# Microcontroller.net
KiCad netlist of a schematic drawn in Altium Designer
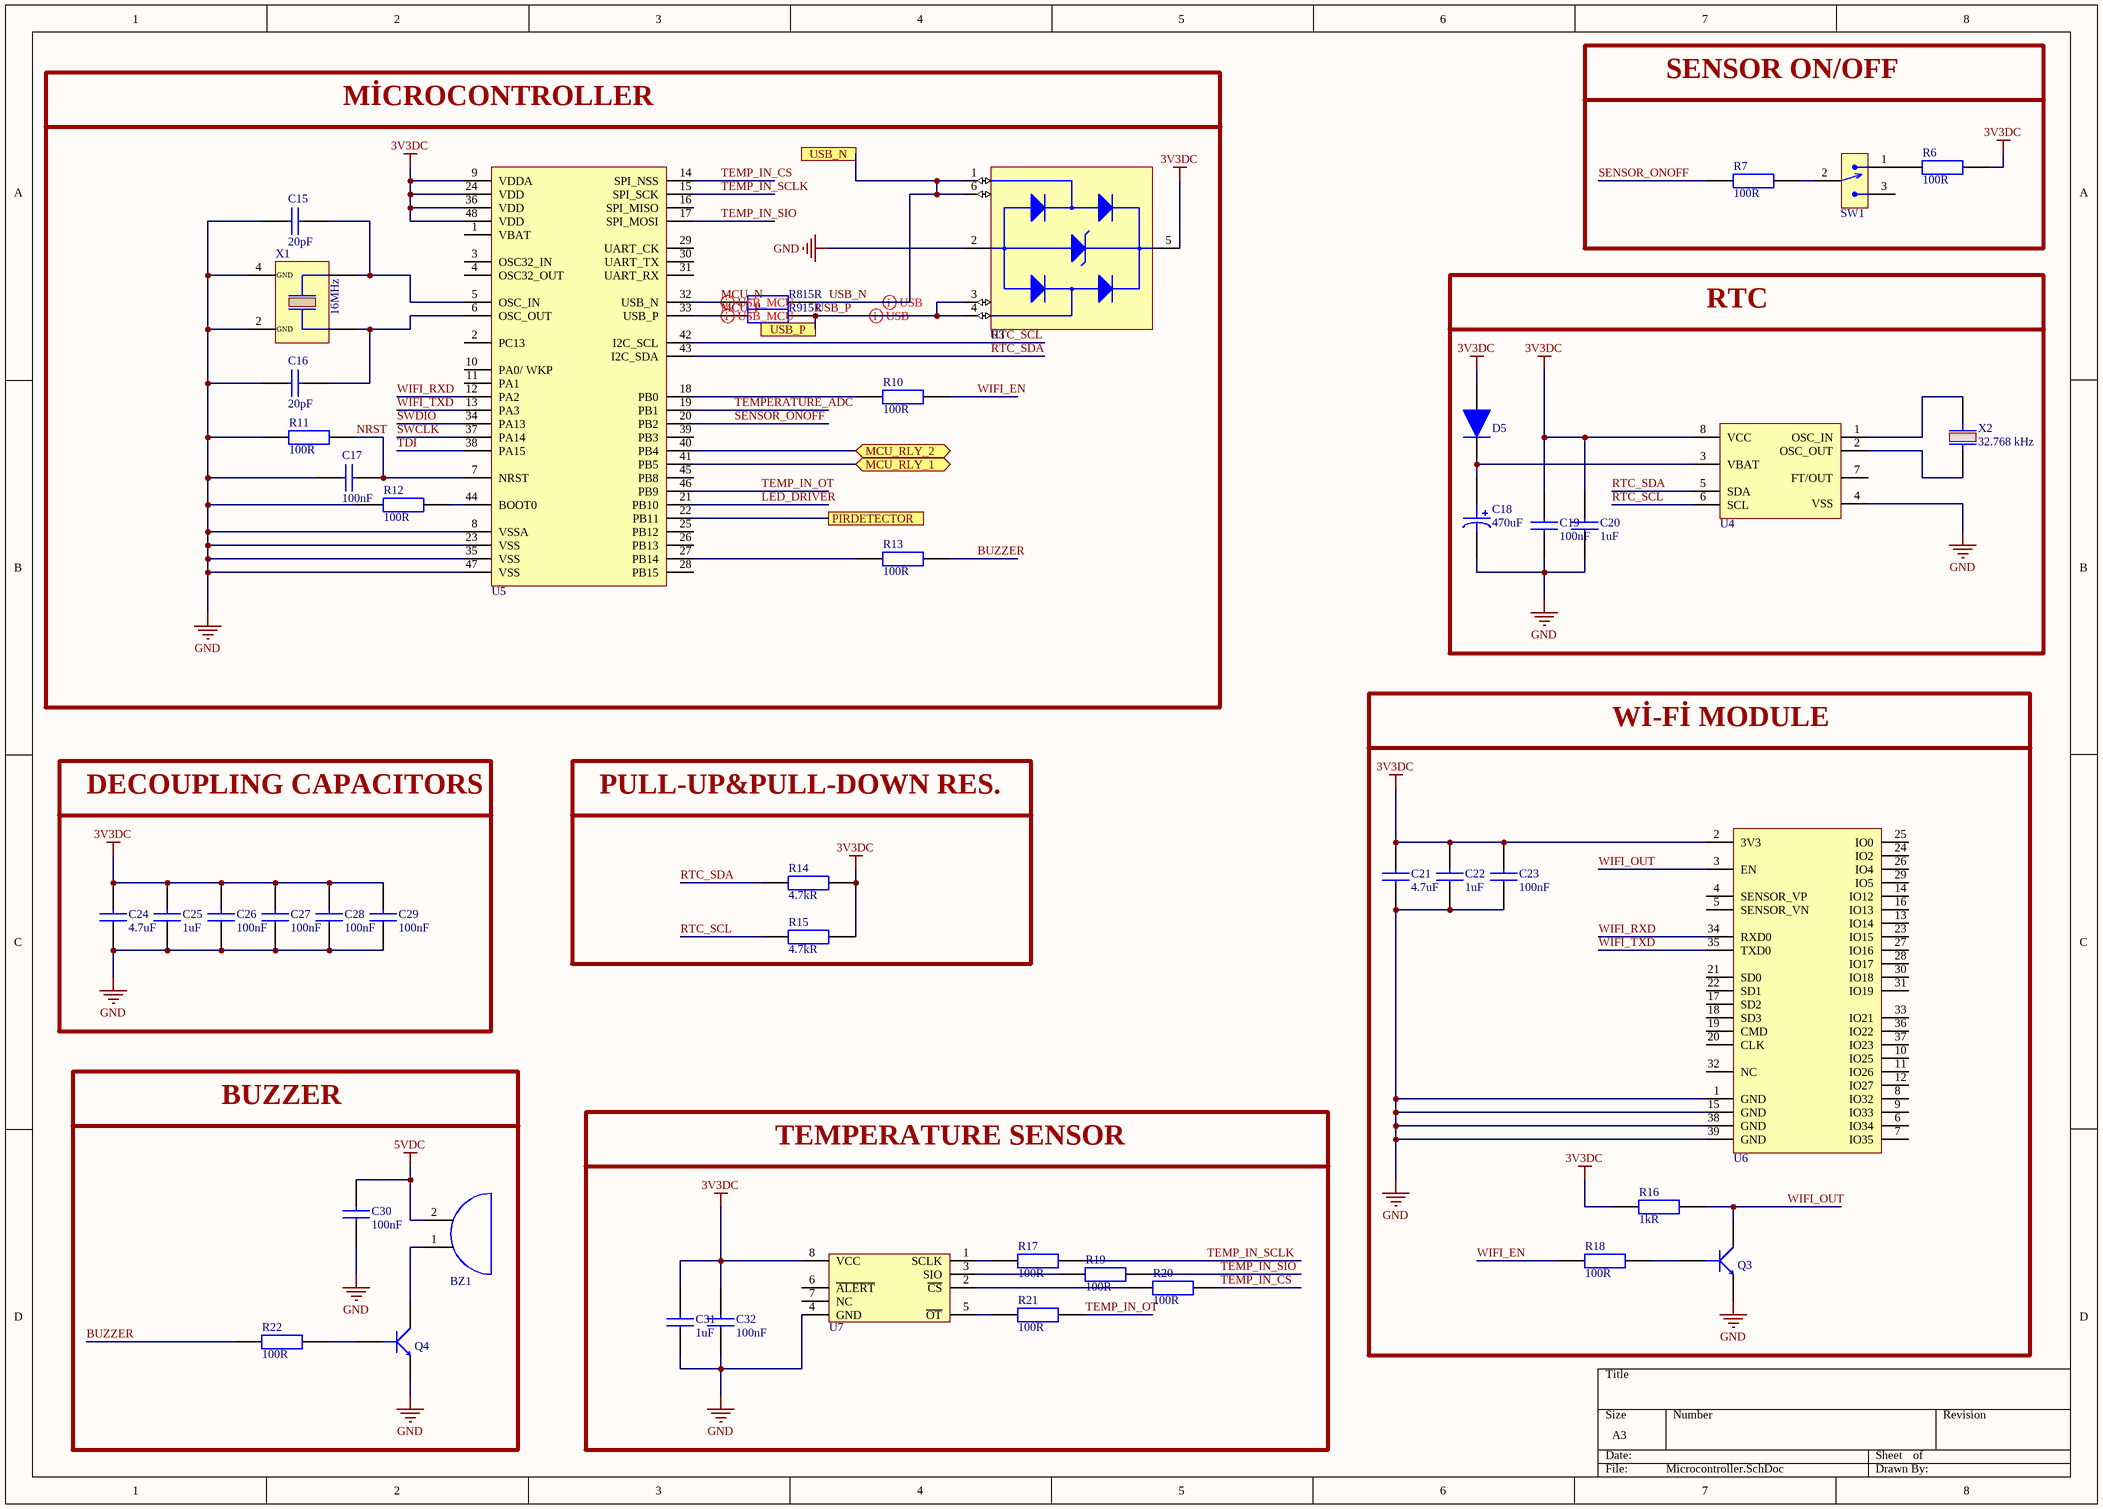
[diagram p0: Microcontroller.SchDoc]

(export (version "E")
  (design (tool "Eeschema 10.0.6"))
  (components
    (comp (ref "BZ1")
      (value "CMI-9605IC-0580T")
      (footprint "CMI-9605IC-0580T")
      (description "Buzzers Indicator, Internally Driven Magnetic 30mA 2.7kHz 80dB @ 5V, 10cm Through Hole PC Pins")
      (fields (field (name "MANUFACTURER") "CUI Devices") (field (name "DESIGNED BY") "TALAT"))
      (libsource (lib "Udemy_Library") (part "CMI-9605IC-0580T"))
    )
    (comp (ref "C15")
      (value "CL10C200JB8NNNC")
      (footprint "CAP_0603")
      (description "CAP CER 20pF %5 0603 SMD")
      (fields
        (field (name "MANUFACTURER") "Samsung")
        (field (name "TOLERANCE") "5%")
        (field (name "CAPACITANCE") "20pF")
        (field (name "DESIGNED BY") "TALAT")
      )
      (libsource (lib "Udemy_Library") (part "CAP CER 20pF 0603"))
    )
    (comp (ref "C16")
      (value "CL10C200JB8NNNC")
      (footprint "CAP_0603")
      (description "CAP CER 20pF %5 0603 SMD")
      (fields
        (field (name "MANUFACTURER") "Samsung")
        (field (name "TOLERANCE") "5%")
        (field (name "CAPACITANCE") "20pF")
        (field (name "DESIGNED BY") "TALAT")
      )
      (libsource (lib "Udemy_Library") (part "CAP CER 20pF 0603"))
    )
    (comp (ref "C17")
      (value "CL21B104KBCNNNC")
      (footprint "CAP_0805")
      (description "CAP CER 100nF %10 0805")
      (fields
        (field (name "MANUFACTURER") "Samsung")
        (field (name "TOLERANCE") "10%")
        (field (name "CAPACITANCE") "100nF")
        (field (name "DESIGNED BY") "TALAT")
      )
      (libsource (lib "Udemy_Library") (part "CAP CER 100nF 0805"))
    )
    (comp (ref "C18")
      (value "ESH477M050AH4AA")
      (footprint "CAP_RADİAL_D10_P5")
      (description "CAP ALU ELEC 470uF 50V RADIAL")
      (fields
        (field (name "MANUFACTURER") "KEMET")
        (field (name "TOLERANCE") "20%")
        (field (name "CAPACITANCE") "470uF")
        (field (name "DESIGNED BY") "TALAT")
      )
      (libsource (lib "Udemy_Library") (part "CAP ALU ELEC 470uF 50V"))
    )
    (comp (ref "C19")
      (value "CL21B104KBCNNNC")
      (footprint "CAP_0805")
      (description "CAP CER 100nF %10 0805")
      (fields
        (field (name "MANUFACTURER") "Samsung")
        (field (name "TOLERANCE") "10%")
        (field (name "CAPACITANCE") "100nF")
        (field (name "DESIGNED BY") "TALAT")
      )
      (libsource (lib "Udemy_Library") (part "CAP CER 100nF 0805"))
    )
    (comp (ref "C20")
      (value "CL21B105KBFNNNE")
      (footprint "CAP_0805")
      (description "CAP CER 1uF %10 0805")
      (fields
        (field (name "MANUFACTURER") "Samsung")
        (field (name "TOLERANCE") "10%")
        (field (name "CAPACITANCE") "1uF")
        (field (name "DESIGNED BY") "TALAT")
      )
      (libsource (lib "Udemy_Library") (part "CAP CER 1uF 0805"))
    )
    (comp (ref "C21")
      (value "CL21A475KAQNNNE")
      (footprint "CAP_0805")
      (description "CAP CER 4.7uF %10 0805")
      (fields
        (field (name "MANUFACTURER") "Samsung")
        (field (name "TOLERANCE") "10%")
        (field (name "CAPACITANCE") "4.7uF")
        (field (name "DESIGNED BY") "TALAT")
      )
      (libsource (lib "Udemy_Library") (part "CAP CER 4.7uF 0805"))
    )
    (comp (ref "C22")
      (value "CL21B105KBFNNNE")
      (footprint "CAP_0805")
      (description "CAP CER 1uF %10 0805")
      (fields
        (field (name "MANUFACTURER") "Samsung")
        (field (name "TOLERANCE") "10%")
        (field (name "CAPACITANCE") "1uF")
        (field (name "DESIGNED BY") "TALAT")
      )
      (libsource (lib "Udemy_Library") (part "CAP CER 1uF 0805"))
    )
    (comp (ref "C23")
      (value "CL21B104KBCNNNC")
      (footprint "CAP_0805")
      (description "CAP CER 100nF %10 0805")
      (fields
        (field (name "MANUFACTURER") "Samsung")
        (field (name "TOLERANCE") "10%")
        (field (name "CAPACITANCE") "100nF")
        (field (name "DESIGNED BY") "TALAT")
      )
      (libsource (lib "Udemy_Library") (part "CAP CER 100nF 0805"))
    )
    (comp (ref "C24")
      (value "CL21A475KAQNNNE")
      (footprint "CAP_0805")
      (description "CAP CER 4.7uF %10 0805")
      (fields
        (field (name "MANUFACTURER") "Samsung")
        (field (name "TOLERANCE") "10%")
        (field (name "CAPACITANCE") "4.7uF")
        (field (name "DESIGNED BY") "TALAT")
      )
      (libsource (lib "Udemy_Library") (part "CAP CER 4.7uF 0805"))
    )
    (comp (ref "C25")
      (value "CL21B105KBFNNNE")
      (footprint "CAP_0805")
      (description "CAP CER 1uF %10 0805")
      (fields
        (field (name "MANUFACTURER") "Samsung")
        (field (name "TOLERANCE") "10%")
        (field (name "CAPACITANCE") "1uF")
        (field (name "DESIGNED BY") "TALAT")
      )
      (libsource (lib "Udemy_Library") (part "CAP CER 1uF 0805"))
    )
    (comp (ref "C26")
      (value "CL21B104KBCNNNC")
      (footprint "CAP_0805")
      (description "CAP CER 100nF %10 0805")
      (fields
        (field (name "MANUFACTURER") "Samsung")
        (field (name "TOLERANCE") "10%")
        (field (name "CAPACITANCE") "100nF")
        (field (name "DESIGNED BY") "TALAT")
      )
      (libsource (lib "Udemy_Library") (part "CAP CER 100nF 0805"))
    )
    (comp (ref "C27")
      (value "CL21B104KBCNNNC")
      (footprint "CAP_0805")
      (description "CAP CER 100nF %10 0805")
      (fields
        (field (name "MANUFACTURER") "Samsung")
        (field (name "TOLERANCE") "10%")
        (field (name "CAPACITANCE") "100nF")
        (field (name "DESIGNED BY") "TALAT")
      )
      (libsource (lib "Udemy_Library") (part "CAP CER 100nF 0805"))
    )
    (comp (ref "C28")
      (value "CL21B104KBCNNNC")
      (footprint "CAP_0805")
      (description "CAP CER 100nF %10 0805")
      (fields
        (field (name "MANUFACTURER") "Samsung")
        (field (name "TOLERANCE") "10%")
        (field (name "CAPACITANCE") "100nF")
        (field (name "DESIGNED BY") "TALAT")
      )
      (libsource (lib "Udemy_Library") (part "CAP CER 100nF 0805"))
    )
    (comp (ref "C29")
      (value "CL21B104KBCNNNC")
      (footprint "CAP_0805")
      (description "CAP CER 100nF %10 0805")
      (fields
        (field (name "MANUFACTURER") "Samsung")
        (field (name "TOLERANCE") "10%")
        (field (name "CAPACITANCE") "100nF")
        (field (name "DESIGNED BY") "TALAT")
      )
      (libsource (lib "Udemy_Library") (part "CAP CER 100nF 0805"))
    )
    (comp (ref "C30")
      (value "CL21B104KBCNNNC")
      (footprint "CAP_0805")
      (description "CAP CER 100nF %10 0805")
      (fields
        (field (name "MANUFACTURER") "Samsung")
        (field (name "TOLERANCE") "10%")
        (field (name "CAPACITANCE") "100nF")
        (field (name "DESIGNED BY") "TALAT")
      )
      (libsource (lib "Udemy_Library") (part "CAP CER 100nF 0805"))
    )
    (comp (ref "C31")
      (value "CL21B105KBFNNNE")
      (footprint "CAP_0805")
      (description "CAP CER 1uF %10 0805")
      (fields
        (field (name "MANUFACTURER") "Samsung")
        (field (name "TOLERANCE") "10%")
        (field (name "CAPACITANCE") "1uF")
        (field (name "DESIGNED BY") "TALAT")
      )
      (libsource (lib "Udemy_Library") (part "CAP CER 1uF 0805"))
    )
    (comp (ref "C32")
      (value "CL21B104KBCNNNC")
      (footprint "CAP_0805")
      (description "CAP CER 100nF %10 0805")
      (fields
        (field (name "MANUFACTURER") "Samsung")
        (field (name "TOLERANCE") "10%")
        (field (name "CAPACITANCE") "100nF")
        (field (name "DESIGNED BY") "TALAT")
      )
      (libsource (lib "Udemy_Library") (part "CAP CER 100nF 0805"))
    )
    (comp (ref "D5")
      (value "1N4148WS")
      (footprint "SOD323F")
      (description "Diode, Single, 75 V, 150 mA, 1 V, 4 ns")
      (fields
        (field (name "MANUFACTURER") "ON Semiconductor / Fairchild")
        (field (name "DESIGNED BY") "TALAT")
      )
      (libsource (lib "Udemy_Library") (part "1N4148WS"))
    )
    (comp (ref "Q3")
      (value "MMBT3904-7-F")
      (footprint "SOT-23F")
      (description "Transistor General Purpose BJT NPN 40 Volt 0.2A Automotive 3-Pin SOT-23")
      (fields (field (name "MANUFACTURER") "Diodes Zetex") (field (name "DESIGNED BY") "TALAT"))
      (libsource (lib "Udemy_Library") (part "MMBT3904-7-F"))
    )
    (comp (ref "Q4")
      (value "MMBT3904-7-F")
      (footprint "SOT-23F")
      (description "Transistor General Purpose BJT NPN 40 Volt 0.2A Automotive 3-Pin SOT-23")
      (fields (field (name "MANUFACTURER") "Diodes Zetex") (field (name "DESIGNED BY") "TALAT"))
      (libsource (lib "Udemy_Library") (part "MMBT3904-7-F"))
    )
    (comp (ref "R6")
      (value "RC0603JR-07100RL")
      (footprint "RES_0603")
      (description "RES 100 %5 OHM 0603 SMD")
      (fields
        (field (name "MANUFACTURER") "Yageo")
        (field (name "TOLERANCE") "5%")
        (field (name "RESISTANCE") "100R")
        (field (name "DESIGNED BY") "TALAT")
      )
      (libsource (lib "") (part "RES 100 OHM 0603_1"))
    )
    (comp (ref "R7")
      (value "RC0603JR-07100RL")
      (footprint "RES_0603")
      (description "RES 100 %5 OHM 0603 SMD")
      (fields
        (field (name "MANUFACTURER") "Yageo")
        (field (name "TOLERANCE") "5%")
        (field (name "RESISTANCE") "100R")
        (field (name "DESIGNED BY") "TALAT")
      )
      (libsource (lib "") (part "RES 100 OHM 0603_1"))
    )
    (comp (ref "R8")
      (value "RC0603JR-0715RL")
      (footprint "RES_0603")
      (description "RES 15 %5 OHM 0603 SMD")
      (fields
        (field (name "MANUFACTURER") "Yageo")
        (field (name "TOLERANCE") "5%")
        (field (name "RESISTANCE") "15R")
        (field (name "DESIGNED BY") "TALAT")
      )
      (libsource (lib "Udemy_Library") (part "RES 15 OHM 0603"))
    )
    (comp (ref "R9")
      (value "RC0603JR-0715RL")
      (footprint "RES_0603")
      (description "RES 15 %5 OHM 0603 SMD")
      (fields
        (field (name "MANUFACTURER") "Yageo")
        (field (name "TOLERANCE") "5%")
        (field (name "RESISTANCE") "15R")
        (field (name "DESIGNED BY") "TALAT")
      )
      (libsource (lib "Udemy_Library") (part "RES 15 OHM 0603"))
    )
    (comp (ref "R10")
      (value "RC0603JR-07100RL")
      (footprint "RES_0603")
      (description "RES 100 %5 OHM 0603 SMD")
      (fields
        (field (name "MANUFACTURER") "Yageo")
        (field (name "TOLERANCE") "5%")
        (field (name "RESISTANCE") "100R")
        (field (name "DESIGNED BY") "TALAT")
      )
      (libsource (lib "Udemy_Library") (part "RES 100 OHM 0603"))
    )
    (comp (ref "R11")
      (value "RC0603JR-07100RL")
      (footprint "RES_0603")
      (description "RES 100 %5 OHM 0603 SMD")
      (fields
        (field (name "MANUFACTURER") "Yageo")
        (field (name "TOLERANCE") "5%")
        (field (name "RESISTANCE") "100R")
        (field (name "DESIGNED BY") "TALAT")
      )
      (libsource (lib "Udemy_Library") (part "RES 100 OHM 0603"))
    )
    (comp (ref "R12")
      (value "RC0603JR-07100RL")
      (footprint "RES_0603")
      (description "RES 100 %5 OHM 0603 SMD")
      (fields
        (field (name "MANUFACTURER") "Yageo")
        (field (name "TOLERANCE") "5%")
        (field (name "RESISTANCE") "100R")
        (field (name "DESIGNED BY") "TALAT")
      )
      (libsource (lib "Udemy_Library") (part "RES 100 OHM 0603"))
    )
    (comp (ref "R13")
      (value "RC0603JR-07100RL")
      (footprint "RES_0603")
      (description "RES 100 %5 OHM 0603 SMD")
      (fields
        (field (name "MANUFACTURER") "Yageo")
        (field (name "TOLERANCE") "5%")
        (field (name "RESISTANCE") "100R")
        (field (name "DESIGNED BY") "TALAT")
      )
      (libsource (lib "Udemy_Library") (part "RES 100 OHM 0603"))
    )
    (comp (ref "R14")
      (value "RC0603JR-074K7L")
      (footprint "RES_0603")
      (description "RES 4K7 %5 OHM 0603 SMD")
      (fields
        (field (name "MANUFACTURER") "Yageo")
        (field (name "TOLERANCE") "5%")
        (field (name "RESISTANCE") "4.7kR")
        (field (name "DESIGNED BY") "TALAT")
      )
      (libsource (lib "Udemy_Library") (part "RES 4K7 OHM 0603"))
    )
    (comp (ref "R15")
      (value "RC0603JR-074K7L")
      (footprint "RES_0603")
      (description "RES 4K7 %5 OHM 0603 SMD")
      (fields
        (field (name "MANUFACTURER") "Yageo")
        (field (name "TOLERANCE") "5%")
        (field (name "RESISTANCE") "4.7kR")
        (field (name "DESIGNED BY") "TALAT")
      )
      (libsource (lib "Udemy_Library") (part "RES 4K7 OHM 0603"))
    )
    (comp (ref "R16")
      (value "RC0603FR-0710KL")
      (footprint "RES_0603")
      (description "RES 1K %1 OHM 0603 SMD")
      (fields
        (field (name "MANUFACTURER") "Yageo")
        (field (name "MANUFACTURER PART NUMBER") "RC0603JR-071KL")
        (field (name "RESISTANCE") "1kR")
        (field (name "DESIGNED BY") "TALAT")
      )
      (libsource (lib "Udemy_Library") (part "RES 1K OHM 0603"))
    )
    (comp (ref "R17")
      (value "RC0603JR-07100RL")
      (footprint "RES_0603")
      (description "RES 100 %5 OHM 0603 SMD")
      (fields
        (field (name "MANUFACTURER") "Yageo")
        (field (name "TOLERANCE") "5%")
        (field (name "RESISTANCE") "100R")
        (field (name "DESIGNED BY") "TALAT")
      )
      (libsource (lib "Udemy_Library") (part "RES 100 OHM 0603"))
    )
    (comp (ref "R18")
      (value "RC0603JR-07100RL")
      (footprint "RES_0603")
      (description "RES 100 %5 OHM 0603 SMD")
      (fields
        (field (name "MANUFACTURER") "Yageo")
        (field (name "TOLERANCE") "5%")
        (field (name "RESISTANCE") "100R")
        (field (name "DESIGNED BY") "TALAT")
      )
      (libsource (lib "Udemy_Library") (part "RES 100 OHM 0603"))
    )
    (comp (ref "R19")
      (value "RC0603JR-07100RL")
      (footprint "RES_0603")
      (description "RES 100 %5 OHM 0603 SMD")
      (fields
        (field (name "MANUFACTURER") "Yageo")
        (field (name "TOLERANCE") "5%")
        (field (name "RESISTANCE") "100R")
        (field (name "DESIGNED BY") "TALAT")
      )
      (libsource (lib "Udemy_Library") (part "RES 100 OHM 0603"))
    )
    (comp (ref "R20")
      (value "RC0603JR-07100RL")
      (footprint "RES_0603")
      (description "RES 100 %5 OHM 0603 SMD")
      (fields
        (field (name "MANUFACTURER") "Yageo")
        (field (name "TOLERANCE") "5%")
        (field (name "RESISTANCE") "100R")
        (field (name "DESIGNED BY") "TALAT")
      )
      (libsource (lib "Udemy_Library") (part "RES 100 OHM 0603"))
    )
    (comp (ref "R21")
      (value "RC0603JR-07100RL")
      (footprint "RES_0603")
      (description "RES 100 %5 OHM 0603 SMD")
      (fields
        (field (name "MANUFACTURER") "Yageo")
        (field (name "TOLERANCE") "5%")
        (field (name "RESISTANCE") "100R")
        (field (name "DESIGNED BY") "TALAT")
      )
      (libsource (lib "Udemy_Library") (part "RES 100 OHM 0603"))
    )
    (comp (ref "R22")
      (value "RC0603JR-07100RL")
      (footprint "RES_0603")
      (description "RES 100 %5 OHM 0603 SMD")
      (fields
        (field (name "MANUFACTURER") "Yageo")
        (field (name "TOLERANCE") "5%")
        (field (name "RESISTANCE") "100R")
        (field (name "DESIGNED BY") "TALAT")
      )
      (libsource (lib "Udemy_Library") (part "RES 100 OHM 0603"))
    )
    (comp (ref "SW1")
      (value "EG1215AA")
      (footprint "EG1215AA")
      (description "Slide Switch, SPDT, 0.025A, 24V, SMD")
      (fields
        (field (name "MANUFACTURER") "E-Switch")
        (field (name "TOLERANCE") "4.95%")
        (field (name "DESIGNED BY") "TALAT")
      )
      (libsource (lib "Udemy_Library") (part "EG1215AA"))
    )
    (comp (ref "U3")
      (value "USBLC6-2SC6")
      (footprint "SOT23-6L")
      (description "TVS DIODE 5.25V 17V SOT23-6")
      (fields (field (name "MANUFACTURER") "STMicroelectronics") (field (name "DESIGNED BY") "TALAT"))
      (libsource (lib "Udemy_Library") (part "USB PROTECTION"))
    )
    (comp (ref "U4")
      (value "M41T00M6F")
      (footprint "SOIC8")
      (description "IC RTC CLK/CALENDAR I2C 8-SOIC")
      (fields (field (name "MANUFACTURER") "STMicroelectronics") (field (name "DESIGNED BY") "TALAT"))
      (libsource (lib "Udemy_Library") (part "M41T00M6F"))
    )
    (comp (ref "U5")
      (value "STM32F103C6T6A")
      (footprint "LQFP-48")
      (description "MCU 32-bit STM32F ARM Cortex M3 RISC 32KB Flash 2.5V/3.3V 48-Pin LQFP Tray")
      (fields (field (name "MANUFACTURER") "STMicroelectronics") (field (name "DESIGNED BY") "TALAT"))
      (libsource (lib "Udemy_Library") (part "STM32F103C6T6A"))
    )
    (comp (ref "U6")
      (value "ESP32-WROOM-32E (4MB)")
      (footprint "ESP32-32")
      (fields
        (field (name "MANUFACTURER") "Espressif Systems")
        (field (name "MANUFACTURER PART NUMBER") "ESP32-WROOM-32E(4MB)")
        (field (name "DESIGNED BY") "TALAT")
      )
      (libsource (lib "Udemy_Library") (part "ESP32-WROOM-32E (4MB)"))
    )
    (comp (ref "U7")
      (value "MAX6662")
      (footprint "SOIC8")
      (description "Temp Sensor Digital Serial (3-Wire, SPI) 8-Pin SOIC N Tube")
      (fields
        (field (name "MANUFACTURER") "Maxim")
        (field (name "MANUFACTURER PART NUMBER") "MAX6662MSA+")
        (field (name "DESIGNED BY") "TALAT")
      )
      (libsource (lib "Udemy_Library") (part "MAX6662"))
    )
    (comp (ref "X1")
      (value "ECS-160-20-30B-TR")
      (footprint "ECS")
      (description "CRYSTAL 16.0000MHZ 20PF SMD")
      (fields
        (field (name "MANUFACTURER") "ECS International")
        (field (name "TOLERANCE") "50ppm")
        (field (name "FREQUENCY") "16MHz")
        (field (name "DESIGNED BY") "TALAT")
      )
      (libsource (lib "Udemy_Library") (part "CRYSTAL 16MHz"))
    )
    (comp (ref "X2")
      (value "ABS05-32.768KHZ-T")
      (footprint "ABS05")
      (description "Crystal, 32.768 kHz, SMD, 1.6mm x 1mm, 12.5 pF, 20 ppm, ABS05 Series")
      (fields
        (field (name "MANUFACTURER") "Abracon")
        (field (name "TOLERANCE") "20ppm")
        (field (name "OPERATING FREQUENCY") "32.768 kHz")
        (field (name "DESIGNED BY") "TALAT")
      )
      (libsource (lib "Udemy_Library") (part "CRYSTAL 32768kHZ"))
    )
  )
  (nets
    (net (code "1") (name "/BUZZER") (class "Default")
      (node (ref "R13") (pin "2") (pinfunction "2_2") (pintype "passive"))
      (node (ref "R22") (pin "1") (pinfunction "1_1") (pintype "passive"))
    )
    (net (code "2") (name "/LED_DRIVER") (class "Default")
      (node (ref "U5") (pin "21") (pinfunction "PB10_21") (pintype "passive"))
    )
    (net (code "3") (name "/MCU_N") (class "Default")
      (node (ref "R8") (pin "1") (pinfunction "1_1") (pintype "passive"))
      (node (ref "U5") (pin "32") (pinfunction "USB_N_32") (pintype "passive"))
    )
    (net (code "4") (name "/MCU_P") (class "Default")
      (node (ref "R9") (pin "1") (pinfunction "1_1") (pintype "passive"))
      (node (ref "U5") (pin "33") (pinfunction "USB_P_33") (pintype "passive"))
    )
    (net (code "5") (name "/MCU_RLY_1") (class "Default")
      (node (ref "U5") (pin "41") (pinfunction "PB5_41") (pintype "passive"))
    )
    (net (code "6") (name "/MCU_RLY_2") (class "Default")
      (node (ref "U5") (pin "40") (pinfunction "PB4_40") (pintype "passive"))
    )
    (net (code "7") (name "/NRST") (class "Default")
      (node (ref "C17") (pin "2") (pinfunction "2_2") (pintype "passive"))
      (node (ref "R11") (pin "2") (pinfunction "2_2") (pintype "passive"))
      (node (ref "U5") (pin "7") (pinfunction "NRST_7") (pintype "passive"))
    )
    (net (code "8") (name "/PIRDETECTOR") (class "Default")
      (node (ref "U5") (pin "22") (pinfunction "PB11_22") (pintype "passive"))
    )
    (net (code "9") (name "/RTC_SCL") (class "Default")
      (node (ref "R15") (pin "1") (pinfunction "1_1") (pintype "passive"))
      (node (ref "U4") (pin "6") (pinfunction "SCL_6") (pintype "passive"))
      (node (ref "U5") (pin "42") (pinfunction "I2C_SCL_42") (pintype "passive"))
    )
    (net (code "10") (name "/RTC_SDA") (class "Default")
      (node (ref "R14") (pin "1") (pinfunction "1_1") (pintype "passive"))
      (node (ref "U4") (pin "5") (pinfunction "SDA_5") (pintype "passive"))
      (node (ref "U5") (pin "43") (pinfunction "I2C_SDA_43") (pintype "passive"))
    )
    (net (code "11") (name "/SENSOR_ONOFF") (class "Default")
      (node (ref "R7") (pin "2") (pinfunction "2_2") (pintype "passive"))
      (node (ref "U5") (pin "20") (pinfunction "PB2_20") (pintype "passive"))
    )
    (net (code "12") (name "/SWCLK") (class "Default")
      (node (ref "U5") (pin "37") (pinfunction "PA14_37") (pintype "passive"))
    )
    (net (code "13") (name "/SWDIO") (class "Default")
      (node (ref "U5") (pin "34") (pinfunction "PA13_34") (pintype "passive"))
    )
    (net (code "14") (name "/TDI") (class "Default")
      (node (ref "U5") (pin "38") (pinfunction "PA15_38") (pintype "passive"))
    )
    (net (code "15") (name "/TEMPERATURE_ADC") (class "Default")
      (node (ref "U5") (pin "19") (pinfunction "PB1_19") (pintype "passive"))
    )
    (net (code "16") (name "/TEMP_IN_CS") (class "Default")
      (node (ref "R20") (pin "2") (pinfunction "2_2") (pintype "passive"))
      (node (ref "U5") (pin "14") (pinfunction "SPI_NSS_14") (pintype "passive"))
    )
    (net (code "17") (name "/TEMP_IN_OT") (class "Default")
      (node (ref "R21") (pin "2") (pinfunction "2_2") (pintype "passive"))
      (node (ref "U5") (pin "46") (pinfunction "PB9_46") (pintype "passive"))
    )
    (net (code "18") (name "/TEMP_IN_SCLK") (class "Default")
      (node (ref "R17") (pin "2") (pinfunction "2_2") (pintype "passive"))
      (node (ref "U5") (pin "15") (pinfunction "SPI_SCK_15") (pintype "passive"))
    )
    (net (code "19") (name "/TEMP_IN_SIO") (class "Default")
      (node (ref "R19") (pin "2") (pinfunction "2_2") (pintype "passive"))
      (node (ref "U5") (pin "17") (pinfunction "SPI_MOSI_17") (pintype "passive"))
    )
    (net (code "20") (name "/USB_N") (class "Default")
      (node (ref "R8") (pin "2") (pinfunction "2_2") (pintype "passive"))
      (node (ref "U3") (pin "1") (pinfunction "I/O1_1") (pintype "bidirectional"))
      (node (ref "U3") (pin "6") (pinfunction "I/O1_6") (pintype "bidirectional"))
    )
    (net (code "21") (name "/USB_P") (class "Default")
      (node (ref "R9") (pin "2") (pinfunction "2_2") (pintype "passive"))
      (node (ref "U3") (pin "3") (pinfunction "I/O2_3") (pintype "bidirectional"))
      (node (ref "U3") (pin "4") (pinfunction "I/O2_4") (pintype "bidirectional"))
    )
    (net (code "22") (name "/WIFI_EN") (class "Default")
      (node (ref "R10") (pin "2") (pinfunction "2_2") (pintype "passive"))
      (node (ref "R18") (pin "1") (pinfunction "1_1") (pintype "passive"))
    )
    (net (code "23") (name "/WIFI_OUT") (class "Default")
      (node (ref "Q3") (pin "3") (pinfunction "C_3") (pintype "power_in"))
      (node (ref "R16") (pin "2") (pinfunction "2_2") (pintype "passive"))
      (node (ref "U6") (pin "3") (pinfunction "EN_3") (pintype "passive"))
    )
    (net (code "24") (name "/WIFI_RXD") (class "Default")
      (node (ref "U5") (pin "12") (pinfunction "PA2_12") (pintype "passive"))
      (node (ref "U6") (pin "34") (pinfunction "RXD0_34") (pintype "passive"))
    )
    (net (code "25") (name "/WIFI_TXD") (class "Default")
      (node (ref "U5") (pin "13") (pinfunction "PA3_13") (pintype "passive"))
      (node (ref "U6") (pin "35") (pinfunction "TXD0_35") (pintype "passive"))
    )
    (net (code "26") (name "3V3DC") (class "Default")
      (node (ref "C19") (pin "2") (pinfunction "2_2") (pintype "passive"))
      (node (ref "C20") (pin "2") (pinfunction "2_2") (pintype "passive"))
      (node (ref "C21") (pin "2") (pinfunction "2_2") (pintype "passive"))
      (node (ref "C22") (pin "2") (pinfunction "2_2") (pintype "passive"))
      (node (ref "C23") (pin "2") (pinfunction "2_2") (pintype "passive"))
      (node (ref "C24") (pin "2") (pinfunction "2_2") (pintype "passive"))
      (node (ref "C25") (pin "2") (pinfunction "2_2") (pintype "passive"))
      (node (ref "C26") (pin "2") (pinfunction "2_2") (pintype "passive"))
      (node (ref "C27") (pin "2") (pinfunction "2_2") (pintype "passive"))
      (node (ref "C28") (pin "2") (pinfunction "2_2") (pintype "passive"))
      (node (ref "C29") (pin "2") (pinfunction "2_2") (pintype "passive"))
      (node (ref "C31") (pin "2") (pinfunction "2_2") (pintype "passive"))
      (node (ref "C32") (pin "2") (pinfunction "2_2") (pintype "passive"))
      (node (ref "D5") (pin "2") (pinfunction "2_2") (pintype "power_in"))
      (node (ref "R14") (pin "2") (pinfunction "2_2") (pintype "passive"))
      (node (ref "R15") (pin "2") (pinfunction "2_2") (pintype "passive"))
      (node (ref "R16") (pin "1") (pinfunction "1_1") (pintype "passive"))
      (node (ref "R6") (pin "1") (pinfunction "1_1") (pintype "passive"))
      (node (ref "U3") (pin "5") (pinfunction "VBUS_5") (pintype "power_in"))
      (node (ref "U4") (pin "8") (pinfunction "VCC_8") (pintype "passive"))
      (node (ref "U5") (pin "24") (pinfunction "VDD_24") (pintype "passive"))
      (node (ref "U5") (pin "36") (pinfunction "VDD_36") (pintype "passive"))
      (node (ref "U5") (pin "48") (pinfunction "VDD_48") (pintype "passive"))
      (node (ref "U5") (pin "9") (pinfunction "VDDA_9") (pintype "passive"))
      (node (ref "U6") (pin "2") (pinfunction "3V3_2") (pintype "passive"))
      (node (ref "U7") (pin "8") (pinfunction "VCC_8") (pintype "passive"))
    )
    (net (code "27") (name "5VDC") (class "Default")
      (node (ref "BZ1") (pin "2") (pinfunction "2_2") (pintype "passive"))
      (node (ref "C30") (pin "2") (pinfunction "2_2") (pintype "passive"))
    )
    (net (code "28") (name "GND") (class "Default")
      (node (ref "C15") (pin "1") (pinfunction "1_1") (pintype "passive"))
      (node (ref "C16") (pin "1") (pinfunction "1_1") (pintype "passive"))
      (node (ref "C17") (pin "1") (pinfunction "1_1") (pintype "passive"))
      (node (ref "C18") (pin "2") (pinfunction "2_2") (pintype "passive"))
      (node (ref "C19") (pin "1") (pinfunction "1_1") (pintype "passive"))
      (node (ref "C20") (pin "1") (pinfunction "1_1") (pintype "passive"))
      (node (ref "C21") (pin "1") (pinfunction "1_1") (pintype "passive"))
      (node (ref "C22") (pin "1") (pinfunction "1_1") (pintype "passive"))
      (node (ref "C23") (pin "1") (pinfunction "1_1") (pintype "passive"))
      (node (ref "C24") (pin "1") (pinfunction "1_1") (pintype "passive"))
      (node (ref "C25") (pin "1") (pinfunction "1_1") (pintype "passive"))
      (node (ref "C26") (pin "1") (pinfunction "1_1") (pintype "passive"))
      (node (ref "C27") (pin "1") (pinfunction "1_1") (pintype "passive"))
      (node (ref "C28") (pin "1") (pinfunction "1_1") (pintype "passive"))
      (node (ref "C29") (pin "1") (pinfunction "1_1") (pintype "passive"))
      (node (ref "C30") (pin "1") (pinfunction "1_1") (pintype "passive"))
      (node (ref "C31") (pin "1") (pinfunction "1_1") (pintype "passive"))
      (node (ref "C32") (pin "1") (pinfunction "1_1") (pintype "passive"))
      (node (ref "Q3") (pin "2") (pinfunction "E_2") (pintype "power_in"))
      (node (ref "Q4") (pin "2") (pinfunction "E_2") (pintype "power_in"))
      (node (ref "R11") (pin "1") (pinfunction "1_1") (pintype "passive"))
      (node (ref "R12") (pin "1") (pinfunction "1_1") (pintype "passive"))
      (node (ref "U3") (pin "2") (pinfunction "GND_2") (pintype "power_in"))
      (node (ref "U4") (pin "4") (pinfunction "VSS_4") (pintype "passive"))
      (node (ref "U5") (pin "23") (pinfunction "VSS_23") (pintype "passive"))
      (node (ref "U5") (pin "35") (pinfunction "VSS_35") (pintype "passive"))
      (node (ref "U5") (pin "47") (pinfunction "VSS_47") (pintype "passive"))
      (node (ref "U5") (pin "8") (pinfunction "VSSA_8") (pintype "passive"))
      (node (ref "U6") (pin "1") (pinfunction "GND_1") (pintype "passive"))
      (node (ref "U6") (pin "15") (pinfunction "GND_15") (pintype "passive"))
      (node (ref "U6") (pin "38") (pinfunction "GND_38") (pintype "passive"))
      (node (ref "U6") (pin "39") (pinfunction "GND_39") (pintype "passive"))
      (node (ref "U7") (pin "4") (pinfunction "GND_4") (pintype "passive"))
      (node (ref "X1") (pin "2") (pinfunction "GND_2") (pintype "passive"))
      (node (ref "X1") (pin "4") (pinfunction "GND_4") (pintype "passive"))
    )
    (net (code "29") (name "Net-(Q3-B)") (class "Default")
      (node (ref "Q3") (pin "1") (pinfunction "B_1") (pintype "power_in"))
      (node (ref "R18") (pin "2") (pinfunction "2_2") (pintype "passive"))
    )
    (net (code "30") (name "Net-(Q4-B)") (class "Default")
      (node (ref "Q4") (pin "1") (pinfunction "B_1") (pintype "power_in"))
      (node (ref "R22") (pin "2") (pinfunction "2_2") (pintype "passive"))
    )
    (net (code "31") (name "Net-(Q4-C)") (class "Default")
      (node (ref "BZ1") (pin "1") (pinfunction "1_1") (pintype "passive"))
      (node (ref "Q4") (pin "3") (pinfunction "C_3") (pintype "power_in"))
    )
    (net (code "32") (name "Net-(R6-Pad2)") (class "Default")
      (node (ref "R6") (pin "2") (pinfunction "2_2") (pintype "passive"))
      (node (ref "SW1") (pin "1") (pinfunction "1_1") (pintype "passive"))
    )
    (net (code "33") (name "Net-(R7-Pad1)") (class "Default")
      (node (ref "R7") (pin "1") (pinfunction "1_1") (pintype "passive"))
      (node (ref "SW1") (pin "2") (pinfunction "2_2") (pintype "passive"))
    )
    (net (code "34") (name "Net-(U4-OSC_IN)") (class "Default")
      (node (ref "U4") (pin "1") (pinfunction "OSC_IN_1") (pintype "passive"))
      (node (ref "X2") (pin "2") (pinfunction "2_2") (pintype "passive"))
    )
    (net (code "35") (name "Net-(U4-OSC_OUT)") (class "Default")
      (node (ref "U4") (pin "2") (pinfunction "OSC_OUT_2") (pintype "passive"))
      (node (ref "X2") (pin "1") (pinfunction "1_1") (pintype "passive"))
    )
    (net (code "36") (name "Net-(U4-VBAT)") (class "Default")
      (node (ref "C18") (pin "1") (pinfunction "1_1") (pintype "passive"))
      (node (ref "D5") (pin "1") (pinfunction "1_1") (pintype "power_in"))
      (node (ref "U4") (pin "3") (pinfunction "VBAT_3") (pintype "passive"))
    )
    (net (code "37") (name "Net-(U5-BOOT0)") (class "Default")
      (node (ref "R12") (pin "2") (pinfunction "2_2") (pintype "passive"))
      (node (ref "U5") (pin "44") (pinfunction "BOOT0_44") (pintype "passive"))
    )
    (net (code "38") (name "Net-(U5-OSC_IN)") (class "Default")
      (node (ref "C15") (pin "2") (pinfunction "2_2") (pintype "passive"))
      (node (ref "U5") (pin "5") (pinfunction "OSC_IN_5") (pintype "passive"))
      (node (ref "X1") (pin "3") (pinfunction "3_3") (pintype "passive"))
    )
    (net (code "39") (name "Net-(U5-OSC_OUT)") (class "Default")
      (node (ref "C16") (pin "2") (pinfunction "2_2") (pintype "passive"))
      (node (ref "U5") (pin "6") (pinfunction "OSC_OUT_6") (pintype "passive"))
      (node (ref "X1") (pin "1") (pinfunction "1_1") (pintype "passive"))
    )
    (net (code "40") (name "Net-(U5-PB0)") (class "Default")
      (node (ref "R10") (pin "1") (pinfunction "1_1") (pintype "passive"))
      (node (ref "U5") (pin "18") (pinfunction "PB0_18") (pintype "passive"))
    )
    (net (code "41") (name "Net-(U5-PB14)") (class "Default")
      (node (ref "R13") (pin "1") (pinfunction "1_1") (pintype "passive"))
      (node (ref "U5") (pin "27") (pinfunction "PB14_27") (pintype "passive"))
    )
    (net (code "42") (name "Net-(U7-SCLK)") (class "Default")
      (node (ref "R17") (pin "1") (pinfunction "1_1") (pintype "passive"))
      (node (ref "U7") (pin "1") (pinfunction "SCLK_1") (pintype "passive"))
    )
    (net (code "43") (name "Net-(U7-SIO)") (class "Default")
      (node (ref "R19") (pin "1") (pinfunction "1_1") (pintype "passive"))
      (node (ref "U7") (pin "3") (pinfunction "SIO_3") (pintype "passive"))
    )
    (net (code "44") (name "Net-(U7-~{CS})") (class "Default")
      (node (ref "R20") (pin "1") (pinfunction "1_1") (pintype "passive"))
      (node (ref "U7") (pin "2") (pinfunction "~{CS}_2") (pintype "passive"))
    )
    (net (code "45") (name "Net-(U7-~{OT})") (class "Default")
      (node (ref "R21") (pin "1") (pinfunction "1_1") (pintype "passive"))
      (node (ref "U7") (pin "5") (pinfunction "~{OT}_5") (pintype "passive"))
    )
    (net (code "46") (name "unconnected-(SW1-Pad3)") (class "Default")
      (node (ref "SW1") (pin "3") (pinfunction "3_3") (pintype "passive"))
    )
    (net (code "47") (name "unconnected-(U4-FT{slash}OUT-Pad7)") (class "Default")
      (node (ref "U4") (pin "7") (pinfunction "FT/OUT_7") (pintype "passive"))
    )
    (net (code "48") (name "unconnected-(U5-OSC32_IN-Pad3)") (class "Default")
      (node (ref "U5") (pin "3") (pinfunction "OSC32_IN_3") (pintype "passive"))
    )
    (net (code "49") (name "unconnected-(U5-OSC32_OUT-Pad4)") (class "Default")
      (node (ref "U5") (pin "4") (pinfunction "OSC32_OUT_4") (pintype "passive"))
    )
    (net (code "50") (name "unconnected-(U5-PA0{slash}_WKP-Pad10)") (class "Default")
      (node (ref "U5") (pin "10") (pinfunction "PA0/_WKP_10") (pintype "passive"))
    )
    (net (code "51") (name "unconnected-(U5-PA1-Pad11)") (class "Default")
      (node (ref "U5") (pin "11") (pinfunction "PA1_11") (pintype "passive"))
    )
    (net (code "52") (name "unconnected-(U5-PB3-Pad39)") (class "Default")
      (node (ref "U5") (pin "39") (pinfunction "PB3_39") (pintype "passive"))
    )
    (net (code "53") (name "unconnected-(U5-PB8-Pad45)") (class "Default")
      (node (ref "U5") (pin "45") (pinfunction "PB8_45") (pintype "passive"))
    )
    (net (code "54") (name "unconnected-(U5-PB12-Pad25)") (class "Default")
      (node (ref "U5") (pin "25") (pinfunction "PB12_25") (pintype "passive"))
    )
    (net (code "55") (name "unconnected-(U5-PB13-Pad26)") (class "Default")
      (node (ref "U5") (pin "26") (pinfunction "PB13_26") (pintype "passive"))
    )
    (net (code "56") (name "unconnected-(U5-PB15-Pad28)") (class "Default")
      (node (ref "U5") (pin "28") (pinfunction "PB15_28") (pintype "passive"))
    )
    (net (code "57") (name "unconnected-(U5-PC13-Pad2)") (class "Default")
      (node (ref "U5") (pin "2") (pinfunction "PC13_2") (pintype "passive"))
    )
    (net (code "58") (name "unconnected-(U5-SPI_MISO-Pad16)") (class "Default")
      (node (ref "U5") (pin "16") (pinfunction "SPI_MISO_16") (pintype "passive"))
    )
    (net (code "59") (name "unconnected-(U5-UART_CK-Pad29)") (class "Default")
      (node (ref "U5") (pin "29") (pinfunction "UART_CK_29") (pintype "passive"))
    )
    (net (code "60") (name "unconnected-(U5-UART_RX-Pad31)") (class "Default")
      (node (ref "U5") (pin "31") (pinfunction "UART_RX_31") (pintype "passive"))
    )
    (net (code "61") (name "unconnected-(U5-UART_TX-Pad30)") (class "Default")
      (node (ref "U5") (pin "30") (pinfunction "UART_TX_30") (pintype "passive"))
    )
    (net (code "62") (name "unconnected-(U5-VBAT-Pad1)") (class "Default")
      (node (ref "U5") (pin "1") (pinfunction "VBAT_1") (pintype "passive"))
    )
    (net (code "63") (name "unconnected-(U6-CLK-Pad20)") (class "Default")
      (node (ref "U6") (pin "20") (pinfunction "CLK_20") (pintype "passive"))
    )
    (net (code "64") (name "unconnected-(U6-CMD-Pad19)") (class "Default")
      (node (ref "U6") (pin "19") (pinfunction "CMD_19") (pintype "passive"))
    )
    (net (code "65") (name "unconnected-(U6-IO0-Pad25)") (class "Default")
      (node (ref "U6") (pin "25") (pinfunction "IO0_25") (pintype "passive"))
    )
    (net (code "66") (name "unconnected-(U6-IO2-Pad24)") (class "Default")
      (node (ref "U6") (pin "24") (pinfunction "IO2_24") (pintype "passive"))
    )
    (net (code "67") (name "unconnected-(U6-IO4-Pad26)") (class "Default")
      (node (ref "U6") (pin "26") (pinfunction "IO4_26") (pintype "passive"))
    )
    (net (code "68") (name "unconnected-(U6-IO5-Pad29)") (class "Default")
      (node (ref "U6") (pin "29") (pinfunction "IO5_29") (pintype "passive"))
    )
    (net (code "69") (name "unconnected-(U6-IO12-Pad14)") (class "Default")
      (node (ref "U6") (pin "14") (pinfunction "IO12_14") (pintype "passive"))
    )
    (net (code "70") (name "unconnected-(U6-IO13-Pad16)") (class "Default")
      (node (ref "U6") (pin "16") (pinfunction "IO13_16") (pintype "passive"))
    )
    (net (code "71") (name "unconnected-(U6-IO14-Pad13)") (class "Default")
      (node (ref "U6") (pin "13") (pinfunction "IO14_13") (pintype "passive"))
    )
    (net (code "72") (name "unconnected-(U6-IO15-Pad23)") (class "Default")
      (node (ref "U6") (pin "23") (pinfunction "IO15_23") (pintype "passive"))
    )
    (net (code "73") (name "unconnected-(U6-IO16-Pad27)") (class "Default")
      (node (ref "U6") (pin "27") (pinfunction "IO16_27") (pintype "passive"))
    )
    (net (code "74") (name "unconnected-(U6-IO17-Pad28)") (class "Default")
      (node (ref "U6") (pin "28") (pinfunction "IO17_28") (pintype "passive"))
    )
    (net (code "75") (name "unconnected-(U6-IO18-Pad30)") (class "Default")
      (node (ref "U6") (pin "30") (pinfunction "IO18_30") (pintype "passive"))
    )
    (net (code "76") (name "unconnected-(U6-IO19-Pad31)") (class "Default")
      (node (ref "U6") (pin "31") (pinfunction "IO19_31") (pintype "passive"))
    )
    (net (code "77") (name "unconnected-(U6-IO21-Pad33)") (class "Default")
      (node (ref "U6") (pin "33") (pinfunction "IO21_33") (pintype "passive"))
    )
    (net (code "78") (name "unconnected-(U6-IO22-Pad36)") (class "Default")
      (node (ref "U6") (pin "36") (pinfunction "IO22_36") (pintype "passive"))
    )
    (net (code "79") (name "unconnected-(U6-IO23-Pad37)") (class "Default")
      (node (ref "U6") (pin "37") (pinfunction "IO23_37") (pintype "passive"))
    )
    (net (code "80") (name "unconnected-(U6-IO25-Pad10)") (class "Default")
      (node (ref "U6") (pin "10") (pinfunction "IO25_10") (pintype "passive"))
    )
    (net (code "81") (name "unconnected-(U6-IO26-Pad11)") (class "Default")
      (node (ref "U6") (pin "11") (pinfunction "IO26_11") (pintype "passive"))
    )
    (net (code "82") (name "unconnected-(U6-IO27-Pad12)") (class "Default")
      (node (ref "U6") (pin "12") (pinfunction "IO27_12") (pintype "passive"))
    )
    (net (code "83") (name "unconnected-(U6-IO32-Pad8)") (class "Default")
      (node (ref "U6") (pin "8") (pinfunction "IO32_8") (pintype "passive"))
    )
    (net (code "84") (name "unconnected-(U6-IO33-Pad9)") (class "Default")
      (node (ref "U6") (pin "9") (pinfunction "IO33_9") (pintype "passive"))
    )
    (net (code "85") (name "unconnected-(U6-IO34-Pad6)") (class "Default")
      (node (ref "U6") (pin "6") (pinfunction "IO34_6") (pintype "passive"))
    )
    (net (code "86") (name "unconnected-(U6-IO35-Pad7)") (class "Default")
      (node (ref "U6") (pin "7") (pinfunction "IO35_7") (pintype "passive"))
    )
    (net (code "87") (name "unconnected-(U6-NC-Pad32)") (class "Default")
      (node (ref "U6") (pin "32") (pinfunction "NC_32") (pintype "passive"))
    )
    (net (code "88") (name "unconnected-(U6-SD0-Pad21)") (class "Default")
      (node (ref "U6") (pin "21") (pinfunction "SD0_21") (pintype "passive"))
    )
    (net (code "89") (name "unconnected-(U6-SD1-Pad22)") (class "Default")
      (node (ref "U6") (pin "22") (pinfunction "SD1_22") (pintype "passive"))
    )
    (net (code "90") (name "unconnected-(U6-SD2-Pad17)") (class "Default")
      (node (ref "U6") (pin "17") (pinfunction "SD2_17") (pintype "passive"))
    )
    (net (code "91") (name "unconnected-(U6-SD3-Pad18)") (class "Default")
      (node (ref "U6") (pin "18") (pinfunction "SD3_18") (pintype "passive"))
    )
    (net (code "92") (name "unconnected-(U6-SENSOR_VN-Pad5)") (class "Default")
      (node (ref "U6") (pin "5") (pinfunction "SENSOR_VN_5") (pintype "passive"))
    )
    (net (code "93") (name "unconnected-(U6-SENSOR_VP-Pad4)") (class "Default")
      (node (ref "U6") (pin "4") (pinfunction "SENSOR_VP_4") (pintype "passive"))
    )
    (net (code "94") (name "unconnected-(U7-NC-Pad7)") (class "Default")
      (node (ref "U7") (pin "7") (pinfunction "NC_7") (pintype "passive"))
    )
    (net (code "95") (name "unconnected-(U7-~{ALERT}-Pad6)") (class "Default")
      (node (ref "U7") (pin "6") (pinfunction "~{ALERT}_6") (pintype "passive"))
    )
  )
)
